# Main0.net
KiCad netlist of a schematic drawn in Altium Designer
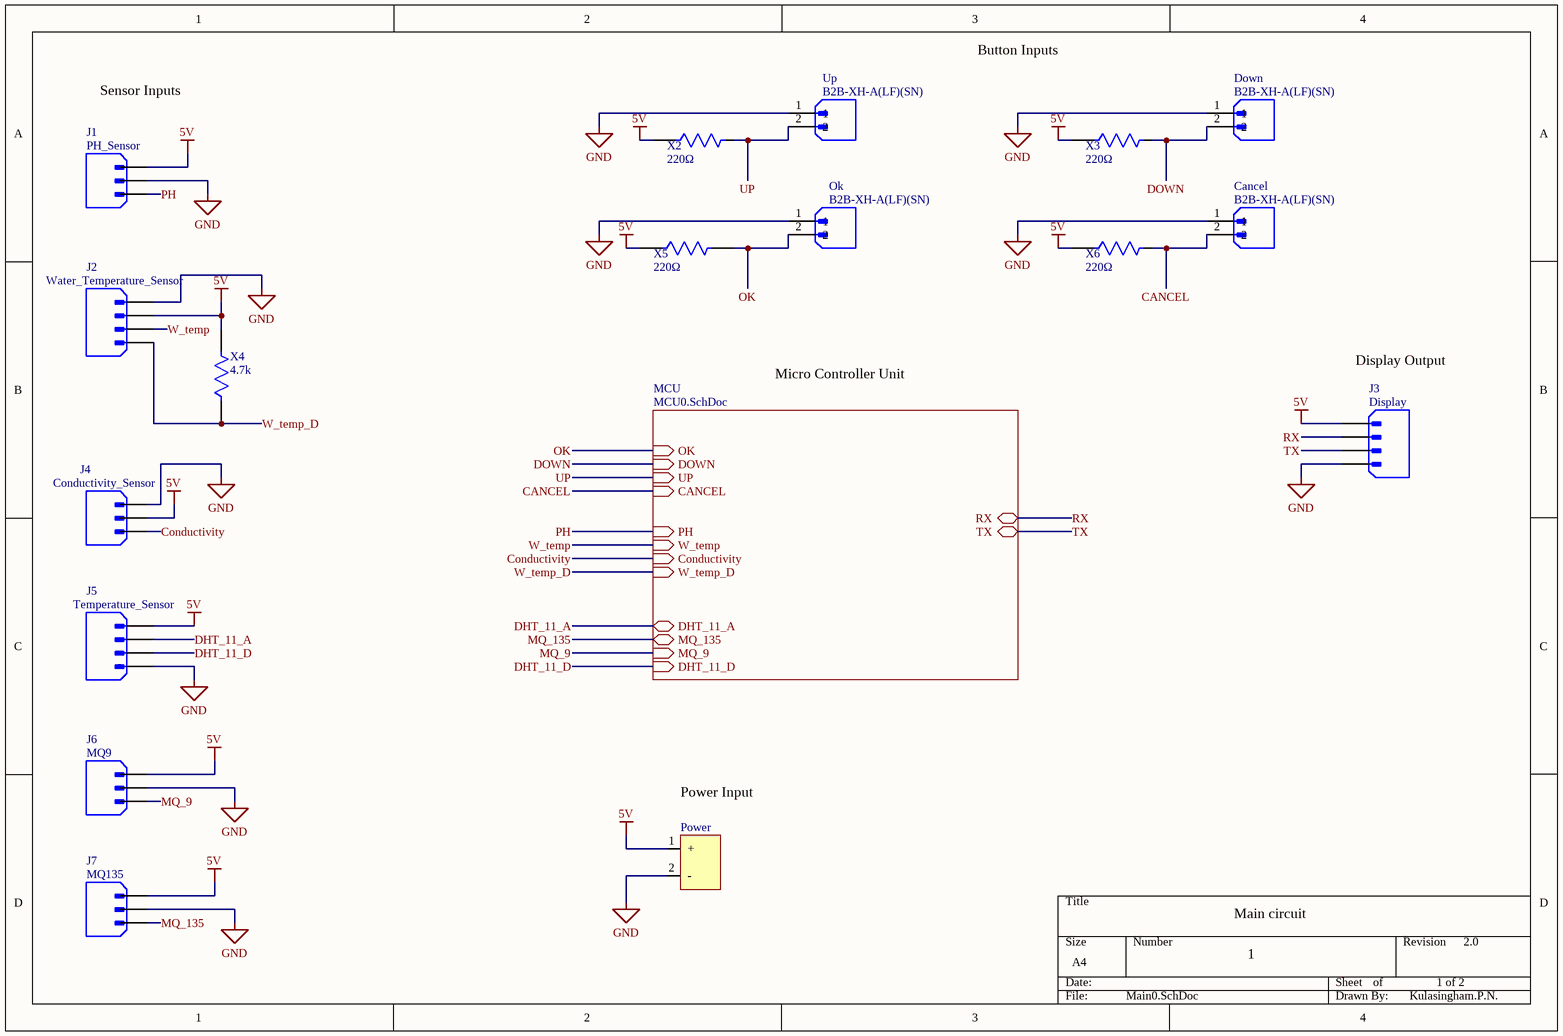
[diagram p0: Main0.SchDoc]

(export (version "E")
  (design (tool "Eeschema 10.0.6"))
  (components
    (comp (ref "Cancel")
      (value "B2B-XH-A(LF)(SN)")
      (footprint "JST_B2B-XH-A(LF)(SN)")
      (description "Connector Header Through Hole 2 position 0.098 (2.50mm)")
      (fields (field (name "MF") "JST Sales America Inc."))
      (libsource (lib "EDR_New") (part "B2B-XH-A(LF)(SN)"))
    )
    (comp (ref "Down")
      (value "B2B-XH-A(LF)(SN)")
      (footprint "JST_B2B-XH-A(LF)(SN)")
      (description "Connector Header Through Hole 2 position 0.098 (2.50mm)")
      (fields (field (name "MF") "JST Sales America Inc."))
      (libsource (lib "EDR_New") (part "B2B-XH-A(LF)(SN)"))
    )
    (comp (ref "J1")
      (value "PH_Sensor")
      (footprint "JST_B3B-XH-A (LF)(SN)")
      (description "Connector Header Through Hole 3 position 0.098 (2.50mm)")
      (fields (field (name "MF") "JST Sales America Inc.") (field (name "MP") "B3B-XH-A (LF)(SN)"))
      (libsource (lib "EDR") (part "B3B-XH-A_(LF)(SN)"))
    )
    (comp (ref "J2")
      (value "Water_Temperature_Sensor")
      (footprint "JST_B4B-XH-A(LF)(SN)")
      (description "Connector Header Through Hole 4 position 0.098 (2.50mm)")
      (fields (field (name "MP") "B4B-XH-A(LF)(SN)") (field (name "MF") "JST Sales"))
      (libsource (lib "") (part "B4B-XH-A(LF)(SN)_1_1"))
    )
    (comp (ref "J3")
      (value "Display")
      (footprint "JST_B4B-XH-A(LF)(SN)")
      (description "Connector Header Through Hole 4 position 0.098 (2.50mm)")
      (fields (field (name "MP") "B4B-XH-A(LF)(SN)") (field (name "MF") "JST Sales"))
      (libsource (lib "EDR") (part "B4B-XH-A(LF)(SN)_1"))
    )
    (comp (ref "J4")
      (value "Conductivity_Sensor")
      (footprint "JST_B3B-XH-A (LF)(SN)")
      (description "Connector Header Through Hole 3 position 0.098 (2.50mm)")
      (fields (field (name "MF") "JST Sales America Inc.") (field (name "MP") "B3B-XH-A (LF)(SN)"))
      (libsource (lib "EDR") (part "B3B-XH-A_(LF)(SN)"))
    )
    (comp (ref "J5")
      (value "Temperature_Sensor")
      (footprint "JST_B4B-XH-A(LF)(SN)")
      (description "Connector Header Through Hole 4 position 0.098 (2.50mm)")
      (fields (field (name "MP") "B4B-XH-A(LF)(SN)") (field (name "MF") "JST Sales"))
      (libsource (lib "") (part "B4B-XH-A(LF)(SN)_1_1"))
    )
    (comp (ref "J6")
      (value "MQ9")
      (footprint "JST_B3B-XH-A (LF)(SN)")
      (description "Connector Header Through Hole 3 position 0.098 (2.50mm)")
      (fields (field (name "MF") "JST Sales America Inc.") (field (name "MP") "B3B-XH-A (LF)(SN)"))
      (libsource (lib "EDR") (part "B3B-XH-A_(LF)(SN)"))
    )
    (comp (ref "J7")
      (value "MQ135")
      (footprint "JST_B3B-XH-A (LF)(SN)")
      (description "Connector Header Through Hole 3 position 0.098 (2.50mm)")
      (fields (field (name "MF") "JST Sales America Inc.") (field (name "MP") "B3B-XH-A (LF)(SN)"))
      (libsource (lib "EDR") (part "B3B-XH-A_(LF)(SN)"))
    )
    (comp (ref "Ok")
      (value "B2B-XH-A(LF)(SN)")
      (footprint "JST_B2B-XH-A(LF)(SN)")
      (description "Connector Header Through Hole 2 position 0.098 (2.50mm)")
      (fields (field (name "MF") "JST Sales America Inc."))
      (libsource (lib "EDR_New") (part "B2B-XH-A(LF)(SN)"))
    )
    (comp (ref "Power")
      (value "TB006-508-02BE")
      (footprint "terminalbox")
      (description "Barrier Strip Terminal Block")
      (fields (field (name "MANUFACTURER") "CUI Devices"))
      (libsource (lib "EDR_New") (part "TB006-508-02BE"))
    )
    (comp (ref "Up")
      (value "B2B-XH-A(LF)(SN)")
      (footprint "JST_B2B-XH-A(LF)(SN)")
      (description "Connector Header Through Hole 2 position 0.098 (2.50mm)")
      (fields (field (name "MF") "JST Sales America Inc."))
      (libsource (lib "EDR_New") (part "B2B-XH-A(LF)(SN)"))
    )
    (comp (ref "X2")
      (value "RCC1206220RFKEA")
      (footprint "RESC3216X60N")
      (description "Thick Film Resistors - SMD 220ohms 1% 100ppm")
      (fields (field (name "MOUSER PART NUMBER") "71-RCC1206220RFKEA") (field (name "RESISTANCE") "220Ω"))
      (libsource (lib "EDR_New") (part "RCC1206220RFKEA"))
    )
    (comp (ref "X3")
      (value "RCC1206220RFKEA")
      (footprint "RESC3216X60N")
      (description "Thick Film Resistors - SMD 220ohms 1% 100ppm")
      (fields (field (name "MOUSER PART NUMBER") "71-RCC1206220RFKEA") (field (name "RESISTANCE") "220Ω"))
      (libsource (lib "EDR_New") (part "RCC1206220RFKEA"))
    )
    (comp (ref "X4")
      (value "RCC1206220RFKEA")
      (footprint "RESC3216X60N")
      (description "Thick Film Resistors - SMD 220ohms 1% 100ppm")
      (fields (field (name "MOUSER PART NUMBER") "71-RCC1206220RFKEA") (field (name "RESISTANCE") "4.7k"))
      (libsource (lib "EDR_New") (part "RCC1206220RFKEA"))
    )
    (comp (ref "X5")
      (value "RCC1206220RFKEA")
      (footprint "RESC3216X60N")
      (description "Thick Film Resistors - SMD 220ohms 1% 100ppm")
      (fields (field (name "MOUSER PART NUMBER") "71-RCC1206220RFKEA") (field (name "RESISTANCE") "220Ω"))
      (libsource (lib "EDR_New") (part "RCC1206220RFKEA"))
    )
    (comp (ref "X6")
      (value "RCC1206220RFKEA")
      (footprint "RESC3216X60N")
      (description "Thick Film Resistors - SMD 220ohms 1% 100ppm")
      (fields (field (name "MOUSER PART NUMBER") "71-RCC1206220RFKEA") (field (name "RESISTANCE") "220Ω"))
      (libsource (lib "EDR_New") (part "RCC1206220RFKEA"))
    )
  )
  (nets
    (net (code "1") (name "/CANCEL") (class "Default")
      (node (ref "Cancel") (pin "2") (pinfunction "2_2") (pintype "passive"))
      (node (ref "X6") (pin "2") (pinfunction "2_2") (pintype "passive"))
    )
    (net (code "2") (name "/Conductivity") (class "Default")
      (node (ref "J4") (pin "3") (pinfunction "3_3") (pintype "passive"))
    )
    (net (code "3") (name "/DHT_11_A") (class "Default")
      (node (ref "J5") (pin "2") (pinfunction "2_2") (pintype "passive"))
    )
    (net (code "4") (name "/DHT_11_D") (class "Default")
      (node (ref "J5") (pin "3") (pinfunction "3_3") (pintype "passive"))
    )
    (net (code "5") (name "/DOWN") (class "Default")
      (node (ref "Down") (pin "2") (pinfunction "2_2") (pintype "passive"))
      (node (ref "X3") (pin "2") (pinfunction "2_2") (pintype "passive"))
    )
    (net (code "6") (name "/MQ_9") (class "Default")
      (node (ref "J6") (pin "3") (pinfunction "3_3") (pintype "passive"))
    )
    (net (code "7") (name "/MQ_135") (class "Default")
      (node (ref "J7") (pin "3") (pinfunction "3_3") (pintype "passive"))
    )
    (net (code "8") (name "/OK") (class "Default")
      (node (ref "Ok") (pin "2") (pinfunction "2_2") (pintype "passive"))
      (node (ref "X5") (pin "2") (pinfunction "2_2") (pintype "passive"))
    )
    (net (code "9") (name "/PH") (class "Default")
      (node (ref "J1") (pin "3") (pinfunction "3_3") (pintype "passive"))
    )
    (net (code "10") (name "/RX") (class "Default")
      (node (ref "J3") (pin "2") (pinfunction "2_2") (pintype "passive"))
    )
    (net (code "11") (name "/TX") (class "Default")
      (node (ref "J3") (pin "3") (pinfunction "3_3") (pintype "passive"))
    )
    (net (code "12") (name "/UP") (class "Default")
      (node (ref "Up") (pin "2") (pinfunction "2_2") (pintype "passive"))
      (node (ref "X2") (pin "2") (pinfunction "2_2") (pintype "passive"))
    )
    (net (code "13") (name "/W_temp") (class "Default")
      (node (ref "J2") (pin "3") (pinfunction "3_3") (pintype "passive"))
    )
    (net (code "14") (name "/W_temp_D") (class "Default")
      (node (ref "J2") (pin "4") (pinfunction "4_4") (pintype "passive"))
      (node (ref "X4") (pin "1") (pinfunction "1_1") (pintype "passive"))
    )
    (net (code "15") (name "5V") (class "Default")
      (node (ref "J1") (pin "1") (pinfunction "1_1") (pintype "passive"))
      (node (ref "J2") (pin "2") (pinfunction "2_2") (pintype "passive"))
      (node (ref "J3") (pin "1") (pinfunction "1_1") (pintype "passive"))
      (node (ref "J4") (pin "2") (pinfunction "2_2") (pintype "passive"))
      (node (ref "J5") (pin "1") (pinfunction "1_1") (pintype "passive"))
      (node (ref "J6") (pin "1") (pinfunction "1_1") (pintype "passive"))
      (node (ref "J7") (pin "1") (pinfunction "1_1") (pintype "passive"))
      (node (ref "Power") (pin "1") (pinfunction "+_1") (pintype "passive"))
      (node (ref "X2") (pin "1") (pinfunction "1_1") (pintype "passive"))
      (node (ref "X3") (pin "1") (pinfunction "1_1") (pintype "passive"))
      (node (ref "X4") (pin "2") (pinfunction "2_2") (pintype "passive"))
      (node (ref "X5") (pin "1") (pinfunction "1_1") (pintype "passive"))
      (node (ref "X6") (pin "1") (pinfunction "1_1") (pintype "passive"))
    )
    (net (code "16") (name "GND") (class "Default")
      (node (ref "Cancel") (pin "1") (pinfunction "1_1") (pintype "passive"))
      (node (ref "Down") (pin "1") (pinfunction "1_1") (pintype "passive"))
      (node (ref "J1") (pin "2") (pinfunction "2_2") (pintype "passive"))
      (node (ref "J2") (pin "1") (pinfunction "1_1") (pintype "passive"))
      (node (ref "J3") (pin "4") (pinfunction "4_4") (pintype "passive"))
      (node (ref "J4") (pin "1") (pinfunction "1_1") (pintype "passive"))
      (node (ref "J5") (pin "4") (pinfunction "4_4") (pintype "passive"))
      (node (ref "J6") (pin "2") (pinfunction "2_2") (pintype "passive"))
      (node (ref "J7") (pin "2") (pinfunction "2_2") (pintype "passive"))
      (node (ref "Ok") (pin "1") (pinfunction "1_1") (pintype "passive"))
      (node (ref "Power") (pin "2") (pinfunction "-_2") (pintype "passive"))
      (node (ref "Up") (pin "1") (pinfunction "1_1") (pintype "passive"))
    )
  )
)
